# trac_temp.net
KiCad netlist of a schematic drawn in EAGLE
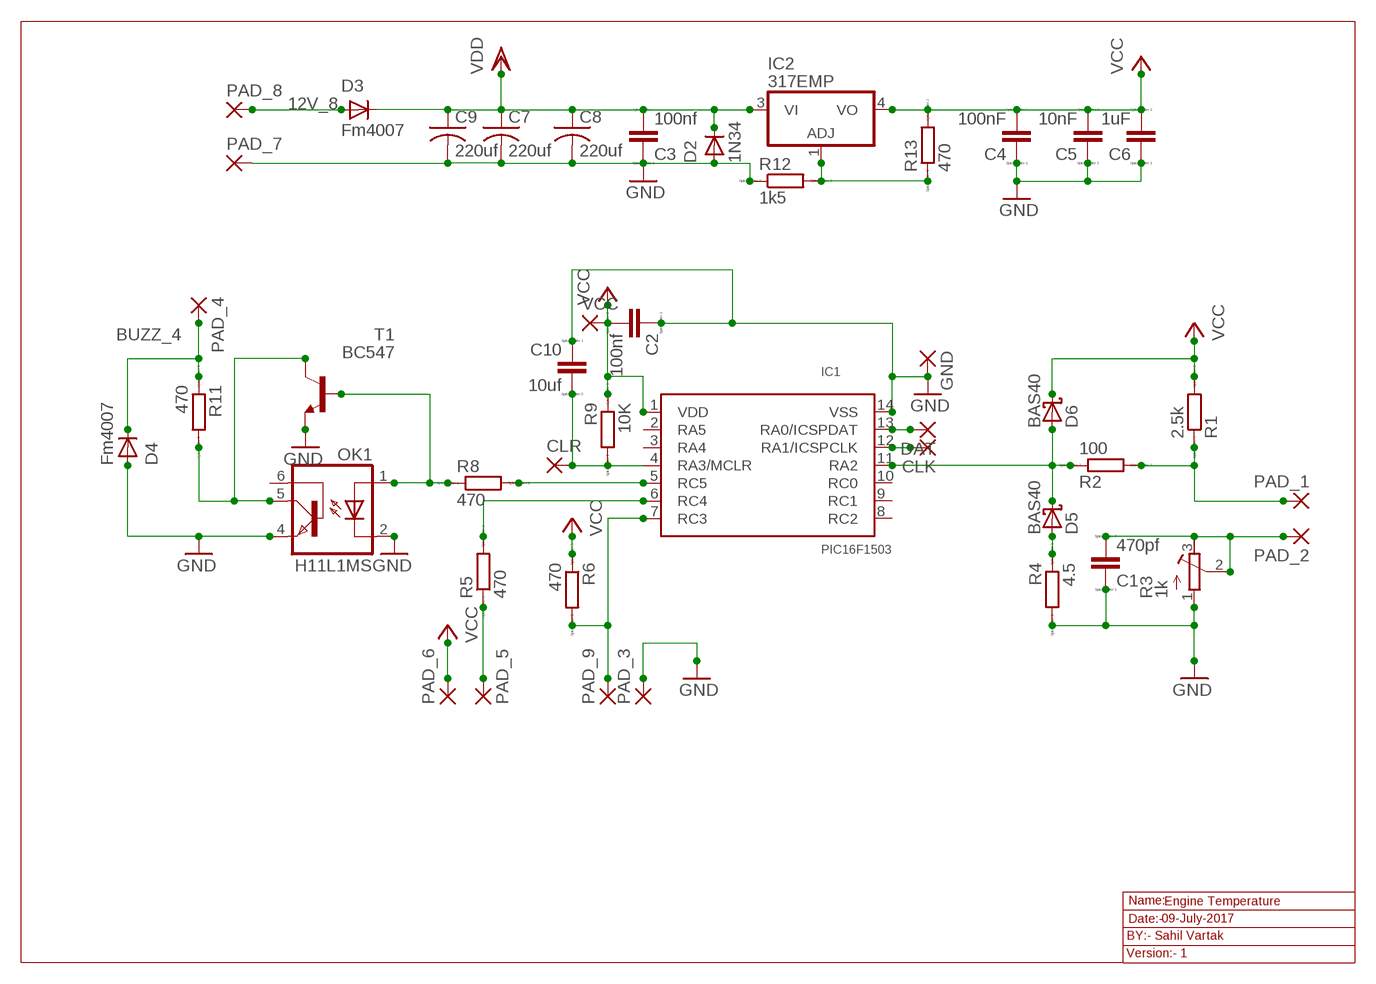
[diagram p0: schematic, sheet 1]

(export (version "E")
  (design (tool "Eeschema 10.0.6"))
  (components
    (comp (ref "C1")
      (value "470pf")
      (footprint "eagle-import:C0603")
      (libsource (lib "eagle-import") (part "CC0603"))
    )
    (comp (ref "C2")
      (value "100nf")
      (footprint "eagle-import:C0603")
      (libsource (lib "eagle-import") (part "CC0603"))
    )
    (comp (ref "C3")
      (value "100nf")
      (footprint "eagle-import:C0603")
      (libsource (lib "eagle-import") (part "CC0603"))
    )
    (comp (ref "C4")
      (value "100nF")
      (footprint "eagle-import:C0603")
      (libsource (lib "eagle-import") (part "CC0603"))
    )
    (comp (ref "C5")
      (value "10nF")
      (footprint "eagle-import:C0603")
      (libsource (lib "eagle-import") (part "CC0603"))
    )
    (comp (ref "C6")
      (value "1uF")
      (footprint "eagle-import:C0603")
      (libsource (lib "eagle-import") (part "CC0603"))
    )
    (comp (ref "C7")
      (value "220uf")
      (footprint "eagle-import:C025-025X050")
      (libsource (lib "eagle-import") (part "C-US025-025X050"))
    )
    (comp (ref "C8")
      (value "220uf")
      (footprint "eagle-import:C025-025X050")
      (libsource (lib "eagle-import") (part "C-US025-025X050"))
    )
    (comp (ref "C9")
      (value "220uf")
      (footprint "eagle-import:C025-025X050")
      (libsource (lib "eagle-import") (part "C-US025-025X050"))
    )
    (comp (ref "C10")
      (value "10uf")
      (footprint "eagle-import:C0603")
      (libsource (lib "eagle-import") (part "CC0603"))
    )
    (comp (ref "CLK")
      (value "1,6/0,8")
      (footprint "eagle-import:1,6_0,8")
      (libsource (lib "eagle-import") (part "1,6/0,8"))
    )
    (comp (ref "CLR")
      (value "1,6/0,8")
      (footprint "eagle-import:1,6_0,8")
      (libsource (lib "eagle-import") (part "1,6/0,8"))
    )
    (comp (ref "D2")
      (value "1N34")
      (footprint "eagle-import:SMA-DO214AC")
      (libsource (lib "eagle-import") (part "GF1"))
    )
    (comp (ref "D3")
      (value "Fm4007")
      (footprint "eagle-import:SMA-DO214AC")
      (libsource (lib "eagle-import") (part "GF1"))
    )
    (comp (ref "D4")
      (value "Fm4007")
      (footprint "eagle-import:SMA-DO214AC")
      (libsource (lib "eagle-import") (part "GF1"))
    )
    (comp (ref "D5")
      (value "BAS40")
      (footprint "eagle-import:SOT23")
      (libsource (lib "eagle-import") (part "BAS40"))
    )
    (comp (ref "D6")
      (value "BAS40")
      (footprint "eagle-import:SOT23")
      (libsource (lib "eagle-import") (part "BAS40"))
    )
    (comp (ref "DAT")
      (value "1,6/0,8")
      (footprint "eagle-import:1,6_0,8")
      (libsource (lib "eagle-import") (part "1,6/0,8"))
    )
    (comp (ref "GND")
      (value "1,6/0,8")
      (footprint "eagle-import:1,6_0,8")
      (libsource (lib "eagle-import") (part "1,6/0,8"))
    )
    (comp (ref "IC1")
      (value "PIC16F1503")
      (footprint "eagle-import:SO-14")
      (libsource (lib "eagle-import") (part "PIC16F1824"))
    )
    (comp (ref "IC2")
      (value "317EMP")
      (footprint "eagle-import:SOT223")
      (libsource (lib "eagle-import") (part "317EMP"))
    )
    (comp (ref "OK1")
      (value "H11L1MS")
      (footprint "eagle-import:DIL6-SMD")
      (libsource (lib "eagle-import") (part "H11LMS1"))
    )
    (comp (ref "PAD_1")
      (value "2,54/1,1")
      (footprint "eagle-import:2,54_1,1")
      (libsource (lib "eagle-import") (part "2,54/1,1"))
    )
    (comp (ref "PAD_2")
      (value "2,54/1,1")
      (footprint "eagle-import:2,54_1,1")
      (libsource (lib "eagle-import") (part "2,54/1,1"))
    )
    (comp (ref "PAD_3")
      (value "2,54/1,1")
      (footprint "eagle-import:2,54_1,1")
      (libsource (lib "eagle-import") (part "2,54/1,1"))
    )
    (comp (ref "PAD_4")
      (value "2,54/1,1")
      (footprint "eagle-import:2,54_1,1")
      (libsource (lib "eagle-import") (part "2,54/1,1"))
    )
    (comp (ref "PAD_5")
      (value "2,54/1,1")
      (footprint "eagle-import:2,54_1,1")
      (libsource (lib "eagle-import") (part "2,54/1,1"))
    )
    (comp (ref "PAD_6")
      (value "2,54/1,1")
      (footprint "eagle-import:2,54_1,1")
      (libsource (lib "eagle-import") (part "2,54/1,1"))
    )
    (comp (ref "PAD_7")
      (value "2,54/1,1")
      (footprint "eagle-import:2,54_1,1")
      (libsource (lib "eagle-import") (part "2,54/1,1"))
    )
    (comp (ref "PAD_8")
      (value "2,54/1,1")
      (footprint "eagle-import:2,54_1,1")
      (libsource (lib "eagle-import") (part "2,54/1,1"))
    )
    (comp (ref "PAD_9")
      (value "2,54/1,1")
      (footprint "eagle-import:2,54_1,1")
      (libsource (lib "eagle-import") (part "2,54/1,1"))
    )
    (comp (ref "R1")
      (value "2.5k")
      (footprint "eagle-import:R0603")
      (libsource (lib "eagle-import") (part "RR0603"))
    )
    (comp (ref "R2")
      (value "100")
      (footprint "eagle-import:R0603")
      (libsource (lib "eagle-import") (part "RR0603"))
    )
    (comp (ref "R3")
      (value "1k")
      (footprint "eagle-import:RTRIM3103")
      (libsource (lib "eagle-import") (part "R-TRIMM3103"))
    )
    (comp (ref "R4")
      (value "4.5")
      (footprint "eagle-import:R0603")
      (libsource (lib "eagle-import") (part "RR0603"))
    )
    (comp (ref "R5")
      (value "470")
      (footprint "eagle-import:R0603")
      (libsource (lib "eagle-import") (part "RR0603"))
    )
    (comp (ref "R6")
      (value "470")
      (footprint "eagle-import:R0603")
      (libsource (lib "eagle-import") (part "RR0603"))
    )
    (comp (ref "R8")
      (value "470")
      (footprint "eagle-import:R0603")
      (libsource (lib "eagle-import") (part "RR0603"))
    )
    (comp (ref "R9")
      (value "10K")
      (footprint "eagle-import:R0603")
      (libsource (lib "eagle-import") (part "RR0603"))
    )
    (comp (ref "R11")
      (value "470")
      (footprint "eagle-import:R0603")
      (libsource (lib "eagle-import") (part "RR0603"))
    )
    (comp (ref "R12")
      (value "1k5")
      (footprint "eagle-import:R0603")
      (libsource (lib "eagle-import") (part "RR0603"))
    )
    (comp (ref "R13")
      (value "470")
      (footprint "eagle-import:R0603")
      (libsource (lib "eagle-import") (part "RR0603"))
    )
    (comp (ref "T1")
      (value "BC547")
      (footprint "eagle-import:TO92")
      (libsource (lib "eagle-import") (part "BC547"))
    )
    (comp (ref "VCC")
      (value "1,6/0,8")
      (footprint "eagle-import:1,6_0,8")
      (libsource (lib "eagle-import") (part "1,6/0,8"))
    )
  )
  (nets
    (net (code "1") (name "/12V_8") (class "Default")
      (node (ref "D3") (pin "A") (pinfunction "A_A") (pintype "passive"))
      (node (ref "PAD_8") (pin "1") (pinfunction "P_1") (pintype "passive"))
    )
    (net (code "2") (name "/BUZZ_4") (class "Default")
      (node (ref "D4") (pin "K") (pinfunction "C_K") (pintype "passive"))
      (node (ref "PAD_4") (pin "1") (pinfunction "P_1") (pintype "passive"))
      (node (ref "R11") (pin "1") (pinfunction "1_1") (pintype "passive"))
    )
    (net (code "3") (name "GND") (class "Default")
      (node (ref "C1") (pin "1") (pinfunction "1_1") (pintype "passive"))
      (node (ref "C10") (pin "1") (pinfunction "1_1") (pintype "passive"))
      (node (ref "C2") (pin "1") (pinfunction "1_1") (pintype "passive"))
      (node (ref "C3") (pin "1") (pinfunction "1_1") (pintype "passive"))
      (node (ref "C4") (pin "1") (pinfunction "1_1") (pintype "passive"))
      (node (ref "C5") (pin "1") (pinfunction "1_1") (pintype "passive"))
      (node (ref "C6") (pin "1") (pinfunction "1_1") (pintype "passive"))
      (node (ref "C7") (pin "2") (pinfunction "2_2") (pintype "passive"))
      (node (ref "C8") (pin "2") (pinfunction "2_2") (pintype "passive"))
      (node (ref "C9") (pin "2") (pinfunction "2_2") (pintype "passive"))
      (node (ref "D2") (pin "A") (pinfunction "A_A") (pintype "passive"))
      (node (ref "D4") (pin "A") (pinfunction "A_A") (pintype "passive"))
      (node (ref "GND") (pin "1") (pinfunction "P_1") (pintype "passive"))
      (node (ref "IC1") (pin "14") (pinfunction "VSS_14") (pintype "bidirectional"))
      (node (ref "OK1") (pin "2") (pinfunction "C_2") (pintype "passive"))
      (node (ref "OK1") (pin "4") (pinfunction "EMI_4") (pintype "passive"))
      (node (ref "PAD_3") (pin "1") (pinfunction "P_1") (pintype "passive"))
      (node (ref "PAD_7") (pin "1") (pinfunction "P_1") (pintype "passive"))
      (node (ref "R12") (pin "1") (pinfunction "1_1") (pintype "passive"))
      (node (ref "R3") (pin "1") (pinfunction "A_1") (pintype "passive"))
      (node (ref "R4") (pin "2") (pinfunction "2_2") (pintype "passive"))
      (node (ref "T1") (pin "1") (pinfunction "E_1") (pintype "passive"))
    )
    (net (code "4") (name "Net-(CLK-P)") (class "Default")
      (node (ref "CLK") (pin "1") (pinfunction "P_1") (pintype "passive"))
      (node (ref "IC1") (pin "12") (pinfunction "RA1/ICSPCLK_12") (pintype "bidirectional"))
    )
    (net (code "5") (name "Net-(CLR-P)") (class "Default")
      (node (ref "C10") (pin "2") (pinfunction "2_2") (pintype "passive"))
      (node (ref "CLR") (pin "1") (pinfunction "P_1") (pintype "passive"))
      (node (ref "IC1") (pin "4") (pinfunction "RA3/MCLR_4") (pintype "bidirectional"))
      (node (ref "R9") (pin "2") (pinfunction "2_2") (pintype "passive"))
    )
    (net (code "6") (name "Net-(D5-A)") (class "Default")
      (node (ref "D5") (pin "1") (pinfunction "A_1") (pintype "passive"))
      (node (ref "R4") (pin "1") (pinfunction "1_1") (pintype "passive"))
    )
    (net (code "7") (name "Net-(D5-C)") (class "Default")
      (node (ref "D5") (pin "3") (pinfunction "C_3") (pintype "passive"))
      (node (ref "D6") (pin "1") (pinfunction "A_1") (pintype "passive"))
      (node (ref "IC1") (pin "11") (pinfunction "RA2_11") (pintype "bidirectional"))
      (node (ref "R2") (pin "1") (pinfunction "1_1") (pintype "passive"))
    )
    (net (code "8") (name "Net-(DAT-P)") (class "Default")
      (node (ref "DAT") (pin "1") (pinfunction "P_1") (pintype "passive"))
      (node (ref "IC1") (pin "13") (pinfunction "RA0/ICSPDAT_13") (pintype "bidirectional"))
    )
    (net (code "9") (name "Net-(IC1-RC3)") (class "Default")
      (node (ref "IC1") (pin "7") (pinfunction "RC3_7") (pintype "bidirectional"))
      (node (ref "PAD_9") (pin "1") (pinfunction "P_1") (pintype "passive"))
      (node (ref "R6") (pin "2") (pinfunction "2_2") (pintype "passive"))
    )
    (net (code "10") (name "Net-(IC1-RC4)") (class "Default")
      (node (ref "IC1") (pin "6") (pinfunction "RC4_6") (pintype "bidirectional"))
      (node (ref "R5") (pin "2") (pinfunction "2_2") (pintype "passive"))
    )
    (net (code "11") (name "Net-(IC1-RC5)") (class "Default")
      (node (ref "IC1") (pin "5") (pinfunction "RC5_5") (pintype "bidirectional"))
      (node (ref "R8") (pin "2") (pinfunction "2_2") (pintype "passive"))
    )
    (net (code "12") (name "Net-(IC2-ADJ)") (class "Default")
      (node (ref "IC2") (pin "1") (pinfunction "ADJ_1") (pintype "input"))
      (node (ref "R12") (pin "2") (pinfunction "2_2") (pintype "passive"))
      (node (ref "R13") (pin "1") (pinfunction "1_1") (pintype "passive"))
    )
    (net (code "13") (name "Net-(OK1-A)") (class "Default")
      (node (ref "OK1") (pin "1") (pinfunction "A_1") (pintype "passive"))
      (node (ref "R8") (pin "1") (pinfunction "1_1") (pintype "passive"))
      (node (ref "T1") (pin "2") (pinfunction "B_2") (pintype "passive"))
    )
    (net (code "14") (name "Net-(OK1-COL)") (class "Default")
      (node (ref "OK1") (pin "5") (pinfunction "COL_5") (pintype "passive"))
      (node (ref "R11") (pin "2") (pinfunction "2_2") (pintype "passive"))
      (node (ref "T1") (pin "3") (pinfunction "C_3") (pintype "passive"))
    )
    (net (code "15") (name "Net-(PAD_1-P)") (class "Default")
      (node (ref "PAD_1") (pin "1") (pinfunction "P_1") (pintype "passive"))
      (node (ref "R1") (pin "1") (pinfunction "1_1") (pintype "passive"))
      (node (ref "R2") (pin "2") (pinfunction "2_2") (pintype "passive"))
    )
    (net (code "16") (name "Net-(PAD_2-P)") (class "Default")
      (node (ref "C1") (pin "2") (pinfunction "2_2") (pintype "passive"))
      (node (ref "PAD_2") (pin "1") (pinfunction "P_1") (pintype "passive"))
      (node (ref "R3") (pin "2") (pinfunction "S_2") (pintype "passive"))
      (node (ref "R3") (pin "3") (pinfunction "E_3") (pintype "passive"))
    )
    (net (code "17") (name "Net-(PAD_5-P)") (class "Default")
      (node (ref "PAD_5") (pin "1") (pinfunction "P_1") (pintype "passive"))
      (node (ref "R5") (pin "1") (pinfunction "1_1") (pintype "passive"))
    )
    (net (code "18") (name "VCC") (class "Default")
      (node (ref "C2") (pin "2") (pinfunction "2_2") (pintype "passive"))
      (node (ref "C4") (pin "2") (pinfunction "2_2") (pintype "passive"))
      (node (ref "C5") (pin "2") (pinfunction "2_2") (pintype "passive"))
      (node (ref "C6") (pin "2") (pinfunction "2_2") (pintype "passive"))
      (node (ref "D6") (pin "3") (pinfunction "C_3") (pintype "passive"))
      (node (ref "IC1") (pin "1") (pinfunction "VDD_1") (pintype "bidirectional"))
      (node (ref "IC2") (pin "4") (pinfunction "VO_4") (pintype "passive"))
      (node (ref "PAD_6") (pin "1") (pinfunction "P_1") (pintype "passive"))
      (node (ref "R1") (pin "2") (pinfunction "2_2") (pintype "passive"))
      (node (ref "R13") (pin "2") (pinfunction "2_2") (pintype "passive"))
      (node (ref "R6") (pin "1") (pinfunction "1_1") (pintype "passive"))
      (node (ref "R9") (pin "1") (pinfunction "1_1") (pintype "passive"))
      (node (ref "VCC") (pin "1") (pinfunction "P_1") (pintype "passive"))
    )
    (net (code "19") (name "VDD") (class "Default")
      (node (ref "C3") (pin "2") (pinfunction "2_2") (pintype "passive"))
      (node (ref "C7") (pin "1") (pinfunction "1_1") (pintype "passive"))
      (node (ref "C8") (pin "1") (pinfunction "1_1") (pintype "passive"))
      (node (ref "C9") (pin "1") (pinfunction "1_1") (pintype "passive"))
      (node (ref "D2") (pin "K") (pinfunction "C_K") (pintype "passive"))
      (node (ref "D3") (pin "K") (pinfunction "C_K") (pintype "passive"))
      (node (ref "IC2") (pin "3") (pinfunction "VI_3") (pintype "input"))
    )
    (net (code "20") (name "unconnected-(IC1-RA4-Pad3)") (class "Default")
      (node (ref "IC1") (pin "3") (pinfunction "RA4_3") (pintype "bidirectional"))
    )
    (net (code "21") (name "unconnected-(IC1-RA5-Pad2)") (class "Default")
      (node (ref "IC1") (pin "2") (pinfunction "RA5_2") (pintype "bidirectional"))
    )
    (net (code "22") (name "unconnected-(IC1-RC0-Pad10)") (class "Default")
      (node (ref "IC1") (pin "10") (pinfunction "RC0_10") (pintype "bidirectional"))
    )
    (net (code "23") (name "unconnected-(IC1-RC1-Pad9)") (class "Default")
      (node (ref "IC1") (pin "9") (pinfunction "RC1_9") (pintype "bidirectional"))
    )
    (net (code "24") (name "unconnected-(IC1-RC2-Pad8)") (class "Default")
      (node (ref "IC1") (pin "8") (pinfunction "RC2_8") (pintype "bidirectional"))
    )
    (net (code "25") (name "unconnected-(OK1-BAS-Pad6)") (class "Default")
      (node (ref "OK1") (pin "6") (pinfunction "BAS_6") (pintype "passive"))
    )
  )
)
